# voltametry.net
KiCad netlist of a schematic drawn in EAGLE
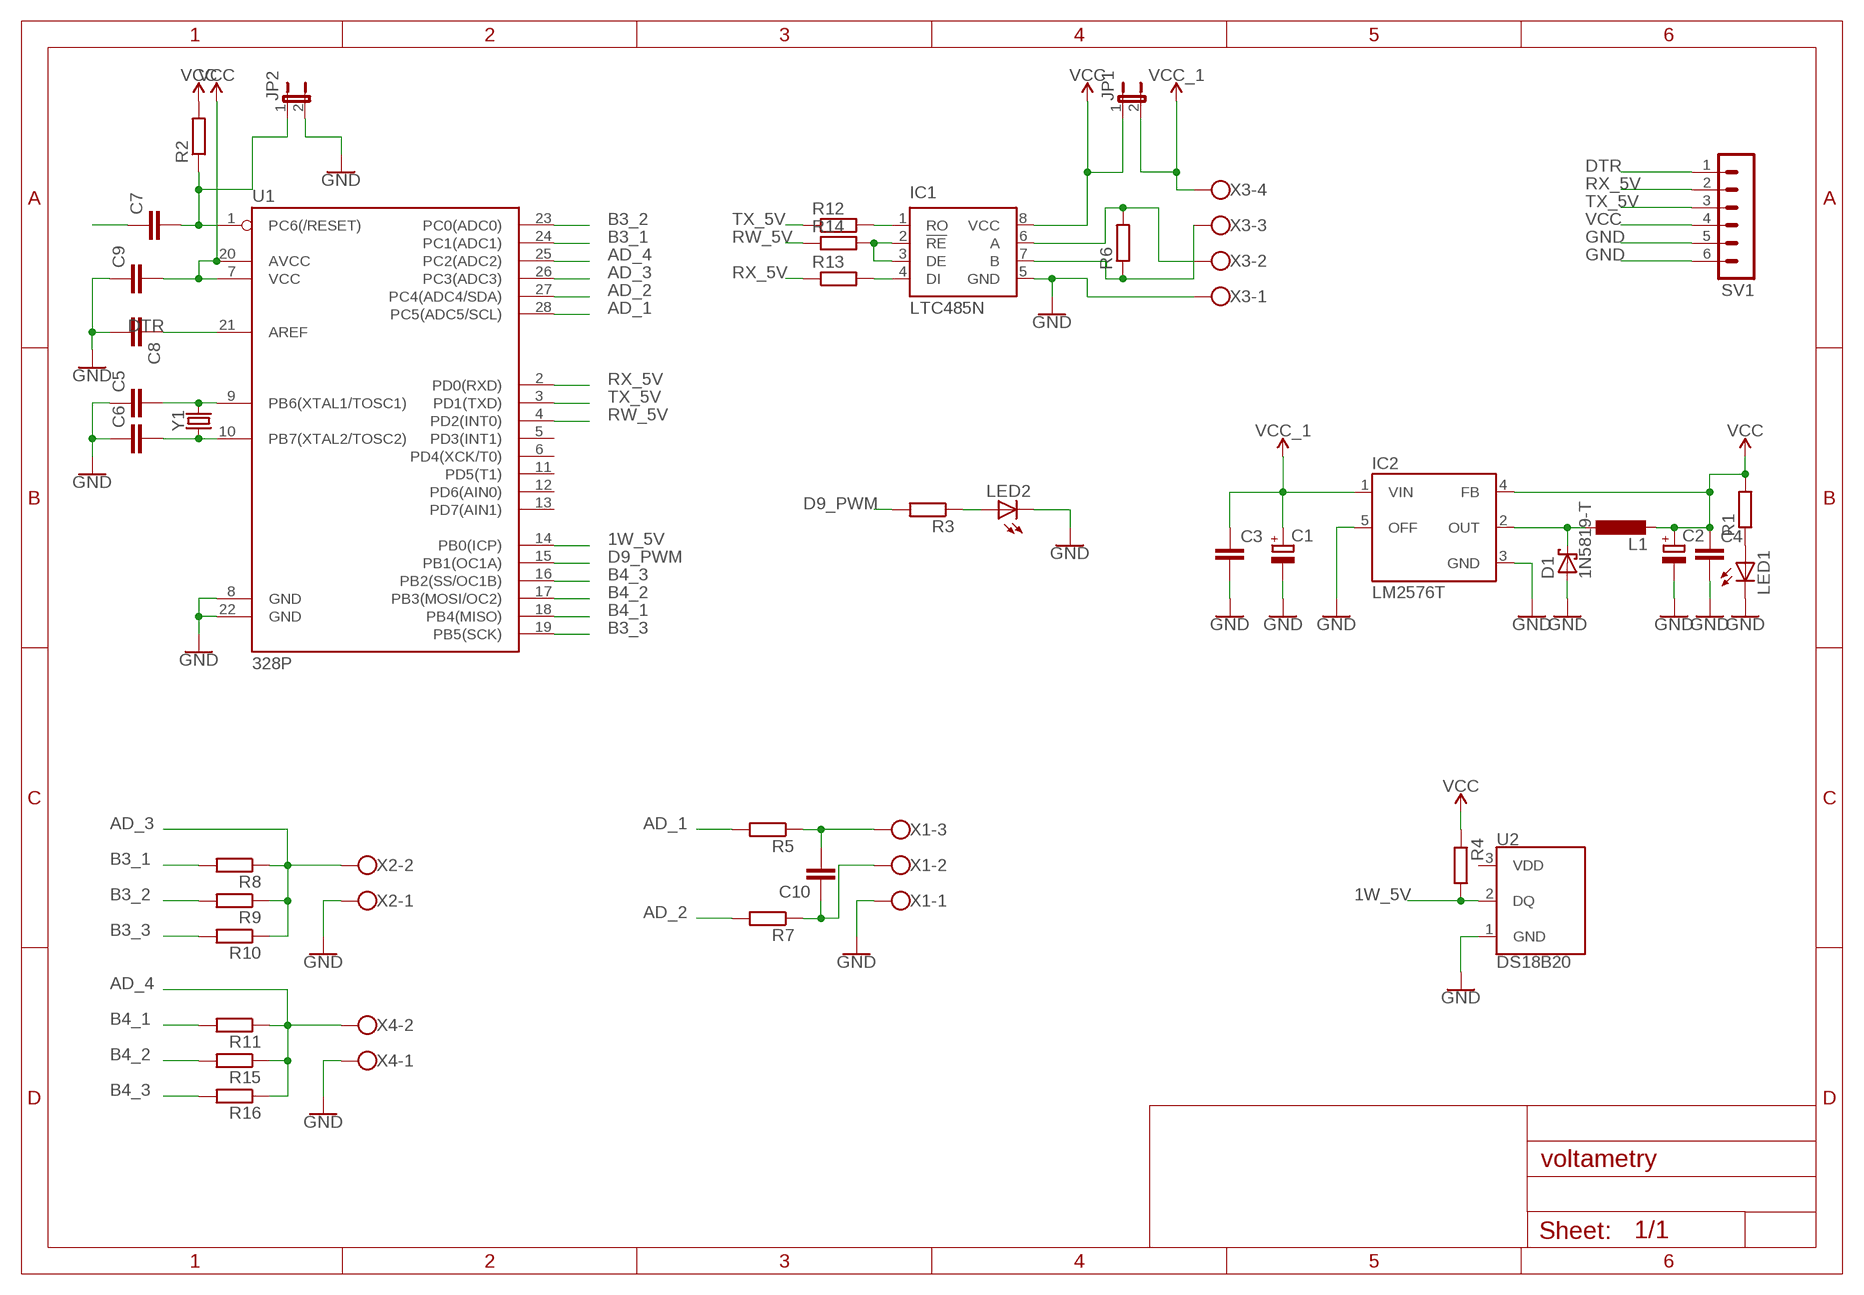
[diagram p0: schematic, sheet 1]

(export (version "E")
  (design (tool "Eeschema 10.0.6"))
  (components
    (comp (ref "C1")
      (value "CPOL-EUE5-10.5")
      (footprint "eagle-import:E5-10,5")
      (libsource (lib "eagle-import") (part "CPOL-EUE5-10.5"))
    )
    (comp (ref "C2")
      (value "CPOL-EUE5-10.5")
      (footprint "eagle-import:E5-10,5")
      (libsource (lib "eagle-import") (part "CPOL-EUE5-10.5"))
    )
    (comp (ref "C3")
      (value "C-EU025-025X050")
      (footprint "eagle-import:C025-025X050")
      (libsource (lib "eagle-import") (part "C-EU025-025X050"))
    )
    (comp (ref "C4")
      (value "C-EU025-025X050")
      (footprint "eagle-import:C025-025X050")
      (libsource (lib "eagle-import") (part "C-EU025-025X050"))
    )
    (comp (ref "C5")
      (value "C-EU025-025X050")
      (footprint "eagle-import:C025-025X050")
      (libsource (lib "eagle-import") (part "C-EU025-025X050"))
    )
    (comp (ref "C6")
      (value "C-EU025-025X050")
      (footprint "eagle-import:C025-025X050")
      (libsource (lib "eagle-import") (part "C-EU025-025X050"))
    )
    (comp (ref "C7")
      (value "C-EU025-025X050")
      (footprint "eagle-import:C025-025X050")
      (libsource (lib "eagle-import") (part "C-EU025-025X050"))
    )
    (comp (ref "C8")
      (value "C-EU025-025X050")
      (footprint "eagle-import:C025-025X050")
      (libsource (lib "eagle-import") (part "C-EU025-025X050"))
    )
    (comp (ref "C9")
      (value "C-EU025-025X050")
      (footprint "eagle-import:C025-025X050")
      (libsource (lib "eagle-import") (part "C-EU025-025X050"))
    )
    (comp (ref "C10")
      (value "C-EU025-025X050")
      (footprint "eagle-import:C025-025X050")
      (libsource (lib "eagle-import") (part "C-EU025-025X050"))
    )
    (comp (ref "D1")
      (value "1N5819-T")
      (footprint "eagle-import:DO41-7.6")
      (libsource (lib "eagle-import") (part "1N5819-T"))
    )
    (comp (ref "IC1")
      (value "LTC485N")
      (footprint "eagle-import:DIL08")
      (libsource (lib "eagle-import") (part "LTC485N"))
    )
    (comp (ref "IC2")
      (value "LM2576T")
      (footprint "eagle-import:TO220-5")
      (libsource (lib "eagle-import") (part "LM2576T"))
    )
    (comp (ref "JP1")
      (value "JP1E")
      (footprint "eagle-import:JP1")
      (libsource (lib "eagle-import") (part "JP1E"))
    )
    (comp (ref "JP2")
      (value "JP1E")
      (footprint "eagle-import:JP1")
      (libsource (lib "eagle-import") (part "JP1E"))
    )
    (comp (ref "L1")
      (value "L-EUTJ3-U1")
      (footprint "eagle-import:TJ3-U1")
      (libsource (lib "eagle-import") (part "L-EUTJ3-U1"))
    )
    (comp (ref "LED1")
      (value "LED5MM")
      (footprint "eagle-import:LED5MM")
      (libsource (lib "eagle-import") (part "LED5MM"))
    )
    (comp (ref "LED2")
      (value "LED5MM")
      (footprint "eagle-import:LED5MM")
      (libsource (lib "eagle-import") (part "LED5MM"))
    )
    (comp (ref "R1")
      (value "R-EU_0204/7")
      (footprint "eagle-import:0204_7")
      (libsource (lib "eagle-import") (part "R-EU_0204/7"))
    )
    (comp (ref "R2")
      (value "R-EU_0204/7")
      (footprint "eagle-import:0204_7")
      (libsource (lib "eagle-import") (part "R-EU_0204/7"))
    )
    (comp (ref "R3")
      (value "R-EU_0204/7")
      (footprint "eagle-import:0204_7")
      (libsource (lib "eagle-import") (part "R-EU_0204/7"))
    )
    (comp (ref "R4")
      (value "R-EU_0204/7")
      (footprint "eagle-import:0204_7")
      (libsource (lib "eagle-import") (part "R-EU_0204/7"))
    )
    (comp (ref "R5")
      (value "R-EU_0204/7")
      (footprint "eagle-import:0204_7")
      (libsource (lib "eagle-import") (part "R-EU_0204/7"))
    )
    (comp (ref "R6")
      (value "R-EU_0204/7")
      (footprint "eagle-import:0204_7")
      (libsource (lib "eagle-import") (part "R-EU_0204/7"))
    )
    (comp (ref "R7")
      (value "R-EU_0204/7")
      (footprint "eagle-import:0204_7")
      (libsource (lib "eagle-import") (part "R-EU_0204/7"))
    )
    (comp (ref "R8")
      (value "R-EU_0204/7")
      (footprint "eagle-import:0204_7")
      (libsource (lib "eagle-import") (part "R-EU_0204/7"))
    )
    (comp (ref "R9")
      (value "R-EU_0204/7")
      (footprint "eagle-import:0204_7")
      (libsource (lib "eagle-import") (part "R-EU_0204/7"))
    )
    (comp (ref "R10")
      (value "R-EU_0204/7")
      (footprint "eagle-import:0204_7")
      (libsource (lib "eagle-import") (part "R-EU_0204/7"))
    )
    (comp (ref "R11")
      (value "R-EU_0204/7")
      (footprint "eagle-import:0204_7")
      (libsource (lib "eagle-import") (part "R-EU_0204/7"))
    )
    (comp (ref "R12")
      (value "R-EU_0204/7")
      (footprint "eagle-import:0204_7")
      (libsource (lib "eagle-import") (part "R-EU_0204/7"))
    )
    (comp (ref "R13")
      (value "R-EU_0204/7")
      (footprint "eagle-import:0204_7")
      (libsource (lib "eagle-import") (part "R-EU_0204/7"))
    )
    (comp (ref "R14")
      (value "R-EU_0204/7")
      (footprint "eagle-import:0204_7")
      (libsource (lib "eagle-import") (part "R-EU_0204/7"))
    )
    (comp (ref "R15")
      (value "R-EU_0204/7")
      (footprint "eagle-import:0204_7")
      (libsource (lib "eagle-import") (part "R-EU_0204/7"))
    )
    (comp (ref "R16")
      (value "R-EU_0204/7")
      (footprint "eagle-import:0204_7")
      (libsource (lib "eagle-import") (part "R-EU_0204/7"))
    )
    (comp (ref "SV1")
      (value "MA06-1")
      (footprint "eagle-import:MA06-1")
      (libsource (lib "eagle-import") (part "MA06-1"))
    )
    (comp (ref "U1")
      (value "328P")
      (footprint "eagle-import:DIP28")
      (libsource (lib "eagle-import") (part "ATMEGA328P_PDIP"))
    )
    (comp (ref "U2")
      (value "DS18B20")
      (footprint "eagle-import:TO-92-AMMO")
      (libsource (lib "eagle-import") (part "DS18B20"))
    )
    (comp (ref "X1")
      (value "W237-103")
      (footprint "eagle-import:W237-103")
      (fields (field (name "MPN") "237-103"))
      (libsource (lib "eagle-import") (part "W237-103"))
    )
    (comp (ref "X2")
      (value "W237-102")
      (footprint "eagle-import:W237-102")
      (fields (field (name "MPN") "237-102"))
      (libsource (lib "eagle-import") (part "W237-102"))
    )
    (comp (ref "X3")
      (value "W237-4")
      (footprint "eagle-import:W237-4")
      (libsource (lib "eagle-import") (part "W237-4"))
    )
    (comp (ref "X4")
      (value "W237-102")
      (footprint "eagle-import:W237-102")
      (fields (field (name "MPN") "237-102"))
      (libsource (lib "eagle-import") (part "W237-102"))
    )
    (comp (ref "Y1")
      (value "CRYSTALPTH-HC49US")
      (footprint "eagle-import:HC49US")
      (libsource (lib "eagle-import") (part "CRYSTALPTH-HC49US"))
    )
  )
  (nets
    (net (code "1") (name "/1W_5V") (class "Default")
      (node (ref "R4") (pin "2") (pinfunction "2_2") (pintype "passive"))
      (node (ref "U1") (pin "14") (pinfunction "PB0(ICP)_14") (pintype "bidirectional"))
      (node (ref "U2") (pin "2") (pinfunction "DQ_2") (pintype "bidirectional"))
    )
    (net (code "2") (name "/AD_1") (class "Default")
      (node (ref "R5") (pin "2") (pinfunction "2_2") (pintype "passive"))
      (node (ref "U1") (pin "28") (pinfunction "PC5(ADC5/SCL)_28") (pintype "bidirectional"))
    )
    (net (code "3") (name "/AD_2") (class "Default")
      (node (ref "R7") (pin "2") (pinfunction "2_2") (pintype "passive"))
      (node (ref "U1") (pin "27") (pinfunction "PC4(ADC4/SDA)_27") (pintype "bidirectional"))
    )
    (net (code "4") (name "/AD_3") (class "Default")
      (node (ref "R10") (pin "1") (pinfunction "1_1") (pintype "passive"))
      (node (ref "R8") (pin "1") (pinfunction "1_1") (pintype "passive"))
      (node (ref "R9") (pin "1") (pinfunction "1_1") (pintype "passive"))
      (node (ref "U1") (pin "26") (pinfunction "PC3(ADC3)_26") (pintype "bidirectional"))
      (node (ref "X2") (pin "2") (pinfunction "KL_2") (pintype "passive"))
    )
    (net (code "5") (name "/AD_4") (class "Default")
      (node (ref "R11") (pin "1") (pinfunction "1_1") (pintype "passive"))
      (node (ref "R15") (pin "1") (pinfunction "1_1") (pintype "passive"))
      (node (ref "R16") (pin "1") (pinfunction "1_1") (pintype "passive"))
      (node (ref "U1") (pin "25") (pinfunction "PC2(ADC2)_25") (pintype "bidirectional"))
      (node (ref "X4") (pin "2") (pinfunction "KL_2") (pintype "passive"))
    )
    (net (code "6") (name "/B3_1") (class "Default")
      (node (ref "R8") (pin "2") (pinfunction "2_2") (pintype "passive"))
      (node (ref "U1") (pin "24") (pinfunction "PC1(ADC1)_24") (pintype "bidirectional"))
    )
    (net (code "7") (name "/B3_2") (class "Default")
      (node (ref "R9") (pin "2") (pinfunction "2_2") (pintype "passive"))
      (node (ref "U1") (pin "23") (pinfunction "PC0(ADC0)_23") (pintype "bidirectional"))
    )
    (net (code "8") (name "/B3_3") (class "Default")
      (node (ref "R10") (pin "2") (pinfunction "2_2") (pintype "passive"))
      (node (ref "U1") (pin "19") (pinfunction "PB5(SCK)_19") (pintype "bidirectional"))
    )
    (net (code "9") (name "/B4_1") (class "Default")
      (node (ref "R11") (pin "2") (pinfunction "2_2") (pintype "passive"))
      (node (ref "U1") (pin "18") (pinfunction "PB4(MISO)_18") (pintype "bidirectional"))
    )
    (net (code "10") (name "/B4_2") (class "Default")
      (node (ref "R15") (pin "2") (pinfunction "2_2") (pintype "passive"))
      (node (ref "U1") (pin "17") (pinfunction "PB3(MOSI/OC2)_17") (pintype "bidirectional"))
    )
    (net (code "11") (name "/B4_3") (class "Default")
      (node (ref "R16") (pin "2") (pinfunction "2_2") (pintype "passive"))
      (node (ref "U1") (pin "16") (pinfunction "PB2(SS/OC1B)_16") (pintype "bidirectional"))
    )
    (net (code "12") (name "/D9_PWM") (class "Default")
      (node (ref "R3") (pin "2") (pinfunction "2_2") (pintype "passive"))
      (node (ref "U1") (pin "15") (pinfunction "PB1(OC1A)_15") (pintype "bidirectional"))
    )
    (net (code "13") (name "/DTR") (class "Default")
      (node (ref "C7") (pin "1") (pinfunction "1_1") (pintype "passive"))
      (node (ref "SV1") (pin "1") (pinfunction "1_1") (pintype "passive"))
    )
    (net (code "14") (name "/RW_5V") (class "Default")
      (node (ref "R14") (pin "1") (pinfunction "1_1") (pintype "passive"))
      (node (ref "U1") (pin "4") (pinfunction "PD2(INT0)_4") (pintype "bidirectional"))
    )
    (net (code "15") (name "/RX_5V") (class "Default")
      (node (ref "R13") (pin "1") (pinfunction "1_1") (pintype "passive"))
      (node (ref "SV1") (pin "2") (pinfunction "2_2") (pintype "passive"))
      (node (ref "U1") (pin "2") (pinfunction "PD0(RXD)_2") (pintype "bidirectional"))
    )
    (net (code "16") (name "/TX_5V") (class "Default")
      (node (ref "R12") (pin "1") (pinfunction "1_1") (pintype "passive"))
      (node (ref "SV1") (pin "3") (pinfunction "3_3") (pintype "passive"))
      (node (ref "U1") (pin "3") (pinfunction "PD1(TXD)_3") (pintype "bidirectional"))
    )
    (net (code "17") (name "/VDD") (class "Default")
      (node (ref "U2") (pin "3") (pinfunction "VDD_3") (pintype "power_in"))
    )
    (net (code "18") (name "GND") (class "Default")
      (node (ref "C1") (pin "-") (pinfunction "-_-") (pintype "passive"))
      (node (ref "C2") (pin "-") (pinfunction "-_-") (pintype "passive"))
      (node (ref "C3") (pin "2") (pinfunction "2_2") (pintype "passive"))
      (node (ref "C4") (pin "2") (pinfunction "2_2") (pintype "passive"))
      (node (ref "C5") (pin "1") (pinfunction "1_1") (pintype "passive"))
      (node (ref "C6") (pin "1") (pinfunction "1_1") (pintype "passive"))
      (node (ref "C8") (pin "2") (pinfunction "2_2") (pintype "passive"))
      (node (ref "C9") (pin "1") (pinfunction "1_1") (pintype "passive"))
      (node (ref "D1") (pin "A") (pinfunction "A_A") (pintype "passive"))
      (node (ref "IC1") (pin "5") (pinfunction "GND_5") (pintype "input"))
      (node (ref "IC2") (pin "3") (pinfunction "GND_3") (pintype "power_in"))
      (node (ref "IC2") (pin "5") (pinfunction "OFF_5") (pintype "input"))
      (node (ref "JP2") (pin "2") (pinfunction "2_2") (pintype "passive"))
      (node (ref "LED1") (pin "K") (pinfunction "C_K") (pintype "passive"))
      (node (ref "LED2") (pin "K") (pinfunction "C_K") (pintype "passive"))
      (node (ref "SV1") (pin "5") (pinfunction "5_5") (pintype "passive"))
      (node (ref "SV1") (pin "6") (pinfunction "6_6") (pintype "passive"))
      (node (ref "U1") (pin "22") (pinfunction "GND_22") (pintype "bidirectional"))
      (node (ref "U1") (pin "8") (pinfunction "GND_8") (pintype "bidirectional"))
      (node (ref "U2") (pin "1") (pinfunction "GND_1") (pintype "power_in"))
      (node (ref "X1") (pin "1") (pinfunction "KL_1") (pintype "passive"))
      (node (ref "X2") (pin "1") (pinfunction "KL_1") (pintype "passive"))
      (node (ref "X3") (pin "1") (pinfunction "KL_1") (pintype "passive"))
      (node (ref "X4") (pin "1") (pinfunction "KL_1") (pintype "passive"))
    )
    (net (code "19") (name "Net-(IC1-A)") (class "Default")
      (node (ref "IC1") (pin "6") (pinfunction "A_6") (pintype "bidirectional"))
      (node (ref "R6") (pin "2") (pinfunction "2_2") (pintype "passive"))
      (node (ref "X3") (pin "2") (pinfunction "KL_2") (pintype "passive"))
    )
    (net (code "20") (name "Net-(IC1-B)") (class "Default")
      (node (ref "IC1") (pin "7") (pinfunction "B_7") (pintype "bidirectional"))
      (node (ref "R6") (pin "1") (pinfunction "1_1") (pintype "passive"))
      (node (ref "X3") (pin "3") (pinfunction "KL_3") (pintype "passive"))
    )
    (net (code "21") (name "Net-(IC1-DE)") (class "Default")
      (node (ref "IC1") (pin "2") (pinfunction "~{RE}_2") (pintype "input"))
      (node (ref "IC1") (pin "3") (pinfunction "DE_3") (pintype "input"))
      (node (ref "R14") (pin "2") (pinfunction "2_2") (pintype "passive"))
    )
    (net (code "22") (name "Net-(IC1-DI)") (class "Default")
      (node (ref "IC1") (pin "4") (pinfunction "DI_4") (pintype "input"))
      (node (ref "R13") (pin "2") (pinfunction "2_2") (pintype "passive"))
    )
    (net (code "23") (name "Net-(IC1-RO)") (class "Default")
      (node (ref "IC1") (pin "1") (pinfunction "RO_1") (pintype "output"))
      (node (ref "R12") (pin "2") (pinfunction "2_2") (pintype "passive"))
    )
    (net (code "24") (name "Net-(IC2-OUT)") (class "Default")
      (node (ref "D1") (pin "C") (pinfunction "C_C") (pintype "passive"))
      (node (ref "IC2") (pin "2") (pinfunction "OUT_2") (pintype "output"))
      (node (ref "L1") (pin "1") (pinfunction "1_1") (pintype "passive"))
    )
    (net (code "25") (name "Net-(LED1-PadA)") (class "Default")
      (node (ref "LED1") (pin "A") (pinfunction "A_A") (pintype "passive"))
      (node (ref "R1") (pin "1") (pinfunction "1_1") (pintype "passive"))
    )
    (net (code "26") (name "Net-(LED2-PadA)") (class "Default")
      (node (ref "LED2") (pin "A") (pinfunction "A_A") (pintype "passive"))
      (node (ref "R3") (pin "1") (pinfunction "1_1") (pintype "passive"))
    )
    (net (code "27") (name "Net-(U1-AREF)") (class "Default")
      (node (ref "C8") (pin "1") (pinfunction "1_1") (pintype "passive"))
      (node (ref "U1") (pin "21") (pinfunction "AREF_21") (pintype "bidirectional"))
    )
    (net (code "28") (name "Net-(U1-PB6(XTAL1{slash}TOSC1))") (class "Default")
      (node (ref "C5") (pin "2") (pinfunction "2_2") (pintype "passive"))
      (node (ref "U1") (pin "9") (pinfunction "PB6(XTAL1/TOSC1)_9") (pintype "bidirectional"))
      (node (ref "Y1") (pin "2") (pinfunction "2_2") (pintype "passive"))
    )
    (net (code "29") (name "Net-(U1-PB7(XTAL2{slash}TOSC2))") (class "Default")
      (node (ref "C6") (pin "2") (pinfunction "2_2") (pintype "passive"))
      (node (ref "U1") (pin "10") (pinfunction "PB7(XTAL2/TOSC2)_10") (pintype "bidirectional"))
      (node (ref "Y1") (pin "1") (pinfunction "1_1") (pintype "passive"))
    )
    (net (code "30") (name "Net-(U1-PC6({slash}RESET))") (class "Default")
      (node (ref "C7") (pin "2") (pinfunction "2_2") (pintype "passive"))
      (node (ref "JP2") (pin "1") (pinfunction "1_1") (pintype "passive"))
      (node (ref "R2") (pin "1") (pinfunction "1_1") (pintype "passive"))
      (node (ref "U1") (pin "1") (pinfunction "PC6(/RESET)_1") (pintype "bidirectional"))
    )
    (net (code "31") (name "Net-(X1B-KL)") (class "Default")
      (node (ref "C10") (pin "1") (pinfunction "1_1") (pintype "passive"))
      (node (ref "R7") (pin "1") (pinfunction "1_1") (pintype "passive"))
      (node (ref "X1") (pin "2") (pinfunction "KL_2") (pintype "passive"))
    )
    (net (code "32") (name "Net-(X1C-KL)") (class "Default")
      (node (ref "C10") (pin "2") (pinfunction "2_2") (pintype "passive"))
      (node (ref "R5") (pin "1") (pinfunction "1_1") (pintype "passive"))
      (node (ref "X1") (pin "3") (pinfunction "KL_3") (pintype "passive"))
    )
    (net (code "33") (name "VCC") (class "Default")
      (node (ref "C2") (pin "+") (pinfunction "+_+") (pintype "passive"))
      (node (ref "C4") (pin "1") (pinfunction "1_1") (pintype "passive"))
      (node (ref "C9") (pin "2") (pinfunction "2_2") (pintype "passive"))
      (node (ref "IC1") (pin "8") (pinfunction "VCC_8") (pintype "input"))
      (node (ref "IC2") (pin "4") (pinfunction "FB_4") (pintype "input"))
      (node (ref "JP1") (pin "1") (pinfunction "1_1") (pintype "passive"))
      (node (ref "L1") (pin "2") (pinfunction "2_2") (pintype "passive"))
      (node (ref "R1") (pin "2") (pinfunction "2_2") (pintype "passive"))
      (node (ref "R2") (pin "2") (pinfunction "2_2") (pintype "passive"))
      (node (ref "R4") (pin "1") (pinfunction "1_1") (pintype "passive"))
      (node (ref "SV1") (pin "4") (pinfunction "4_4") (pintype "passive"))
      (node (ref "U1") (pin "20") (pinfunction "AVCC_20") (pintype "bidirectional"))
      (node (ref "U1") (pin "7") (pinfunction "VCC_7") (pintype "bidirectional"))
    )
    (net (code "34") (name "VCC_1") (class "Default")
      (node (ref "C1") (pin "+") (pinfunction "+_+") (pintype "passive"))
      (node (ref "C3") (pin "1") (pinfunction "1_1") (pintype "passive"))
      (node (ref "IC2") (pin "1") (pinfunction "VIN_1") (pintype "power_in"))
      (node (ref "JP1") (pin "2") (pinfunction "2_2") (pintype "passive"))
      (node (ref "X3") (pin "4") (pinfunction "KL_4") (pintype "passive"))
    )
    (net (code "35") (name "unconnected-(U1-PD3(INT1)-Pad5)") (class "Default")
      (node (ref "U1") (pin "5") (pinfunction "PD3(INT1)_5") (pintype "bidirectional"))
    )
    (net (code "36") (name "unconnected-(U1-PD4(XCK{slash}T0)-Pad6)") (class "Default")
      (node (ref "U1") (pin "6") (pinfunction "PD4(XCK/T0)_6") (pintype "bidirectional"))
    )
    (net (code "37") (name "unconnected-(U1-PD5(T1)-Pad11)") (class "Default")
      (node (ref "U1") (pin "11") (pinfunction "PD5(T1)_11") (pintype "bidirectional"))
    )
    (net (code "38") (name "unconnected-(U1-PD6(AIN0)-Pad12)") (class "Default")
      (node (ref "U1") (pin "12") (pinfunction "PD6(AIN0)_12") (pintype "bidirectional"))
    )
    (net (code "39") (name "unconnected-(U1-PD7(AIN1)-Pad13)") (class "Default")
      (node (ref "U1") (pin "13") (pinfunction "PD7(AIN1)_13") (pintype "bidirectional"))
    )
  )
)
